# ArduinoMiniProgrammer.net
KiCad netlist of a schematic drawn in EAGLE
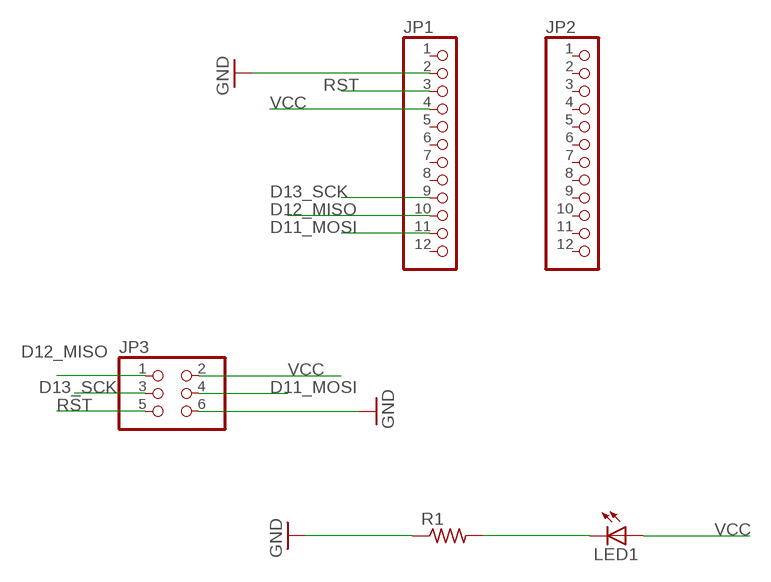
[diagram p0: schematic, sheet 1]

(export (version "E")
  (design (tool "Eeschema 10.0.6"))
  (components
    (comp (ref "JP1")
      (value "PINHD-1X12")
      (footprint "eagle-import:1X12")
      (libsource (lib "eagle-import") (part "PINHD-1X12"))
    )
    (comp (ref "JP2")
      (value "PINHD-1X12")
      (footprint "eagle-import:1X12")
      (libsource (lib "eagle-import") (part "PINHD-1X12"))
    )
    (comp (ref "JP3")
      (value "PINHD-2X3")
      (footprint "eagle-import:2X03")
      (libsource (lib "eagle-import") (part "PINHD-2X3"))
    )
    (comp (ref "LED1")
      (value "LEDCHIPLED_0805")
      (footprint "eagle-import:CHIPLED_0805")
      (libsource (lib "eagle-import") (part "LEDCHIPLED_0805"))
    )
    (comp (ref "R1")
      (value "R-US_R0805")
      (footprint "eagle-import:R0805")
      (libsource (lib "eagle-import") (part "R-US_R0805"))
    )
  )
  (nets
    (net (code "1") (name "/D11_MOSI") (class "Default")
      (node (ref "JP1") (pin "11") (pinfunction "11_11") (pintype "passive"))
      (node (ref "JP3") (pin "4") (pinfunction "4_4") (pintype "passive"))
    )
    (net (code "2") (name "/D12_MISO") (class "Default")
      (node (ref "JP1") (pin "10") (pinfunction "10_10") (pintype "passive"))
      (node (ref "JP3") (pin "1") (pinfunction "1_1") (pintype "passive"))
    )
    (net (code "3") (name "/D13_SCK") (class "Default")
      (node (ref "JP1") (pin "9") (pinfunction "9_9") (pintype "passive"))
      (node (ref "JP3") (pin "3") (pinfunction "3_3") (pintype "passive"))
    )
    (net (code "4") (name "/RST") (class "Default")
      (node (ref "JP1") (pin "3") (pinfunction "3_3") (pintype "passive"))
      (node (ref "JP3") (pin "5") (pinfunction "5_5") (pintype "passive"))
    )
    (net (code "5") (name "/VCC") (class "Default")
      (node (ref "JP1") (pin "4") (pinfunction "4_4") (pintype "passive"))
      (node (ref "JP3") (pin "2") (pinfunction "2_2") (pintype "passive"))
      (node (ref "LED1") (pin "A") (pinfunction "A_A") (pintype "passive"))
    )
    (net (code "6") (name "GND") (class "Default")
      (node (ref "JP1") (pin "2") (pinfunction "2_2") (pintype "passive"))
      (node (ref "JP3") (pin "6") (pinfunction "6_6") (pintype "passive"))
      (node (ref "R1") (pin "1") (pinfunction "1_1") (pintype "passive"))
    )
    (net (code "7") (name "Net-(LED1-PadC)") (class "Default")
      (node (ref "LED1") (pin "C") (pinfunction "C_C") (pintype "passive"))
      (node (ref "R1") (pin "2") (pinfunction "2_2") (pintype "passive"))
    )
    (net (code "8") (name "unconnected-(JP1-Pad1)") (class "Default")
      (node (ref "JP1") (pin "1") (pinfunction "1_1") (pintype "passive"))
    )
    (net (code "9") (name "unconnected-(JP1-Pad5)") (class "Default")
      (node (ref "JP1") (pin "5") (pinfunction "5_5") (pintype "passive"))
    )
    (net (code "10") (name "unconnected-(JP1-Pad6)") (class "Default")
      (node (ref "JP1") (pin "6") (pinfunction "6_6") (pintype "passive"))
    )
    (net (code "11") (name "unconnected-(JP1-Pad7)") (class "Default")
      (node (ref "JP1") (pin "7") (pinfunction "7_7") (pintype "passive"))
    )
    (net (code "12") (name "unconnected-(JP1-Pad8)") (class "Default")
      (node (ref "JP1") (pin "8") (pinfunction "8_8") (pintype "passive"))
    )
    (net (code "13") (name "unconnected-(JP1-Pad12)") (class "Default")
      (node (ref "JP1") (pin "12") (pinfunction "12_12") (pintype "passive"))
    )
    (net (code "14") (name "unconnected-(JP2-Pad1)") (class "Default")
      (node (ref "JP2") (pin "1") (pinfunction "1_1") (pintype "passive"))
    )
    (net (code "15") (name "unconnected-(JP2-Pad2)") (class "Default")
      (node (ref "JP2") (pin "2") (pinfunction "2_2") (pintype "passive"))
    )
    (net (code "16") (name "unconnected-(JP2-Pad3)") (class "Default")
      (node (ref "JP2") (pin "3") (pinfunction "3_3") (pintype "passive"))
    )
    (net (code "17") (name "unconnected-(JP2-Pad4)") (class "Default")
      (node (ref "JP2") (pin "4") (pinfunction "4_4") (pintype "passive"))
    )
    (net (code "18") (name "unconnected-(JP2-Pad5)") (class "Default")
      (node (ref "JP2") (pin "5") (pinfunction "5_5") (pintype "passive"))
    )
    (net (code "19") (name "unconnected-(JP2-Pad6)") (class "Default")
      (node (ref "JP2") (pin "6") (pinfunction "6_6") (pintype "passive"))
    )
    (net (code "20") (name "unconnected-(JP2-Pad7)") (class "Default")
      (node (ref "JP2") (pin "7") (pinfunction "7_7") (pintype "passive"))
    )
    (net (code "21") (name "unconnected-(JP2-Pad8)") (class "Default")
      (node (ref "JP2") (pin "8") (pinfunction "8_8") (pintype "passive"))
    )
    (net (code "22") (name "unconnected-(JP2-Pad9)") (class "Default")
      (node (ref "JP2") (pin "9") (pinfunction "9_9") (pintype "passive"))
    )
    (net (code "23") (name "unconnected-(JP2-Pad10)") (class "Default")
      (node (ref "JP2") (pin "10") (pinfunction "10_10") (pintype "passive"))
    )
    (net (code "24") (name "unconnected-(JP2-Pad11)") (class "Default")
      (node (ref "JP2") (pin "11") (pinfunction "11_11") (pintype "passive"))
    )
    (net (code "25") (name "unconnected-(JP2-Pad12)") (class "Default")
      (node (ref "JP2") (pin "12") (pinfunction "12_12") (pintype "passive"))
    )
  )
)
